# Iout.net
KiCad netlist of a schematic drawn in Altium Designer
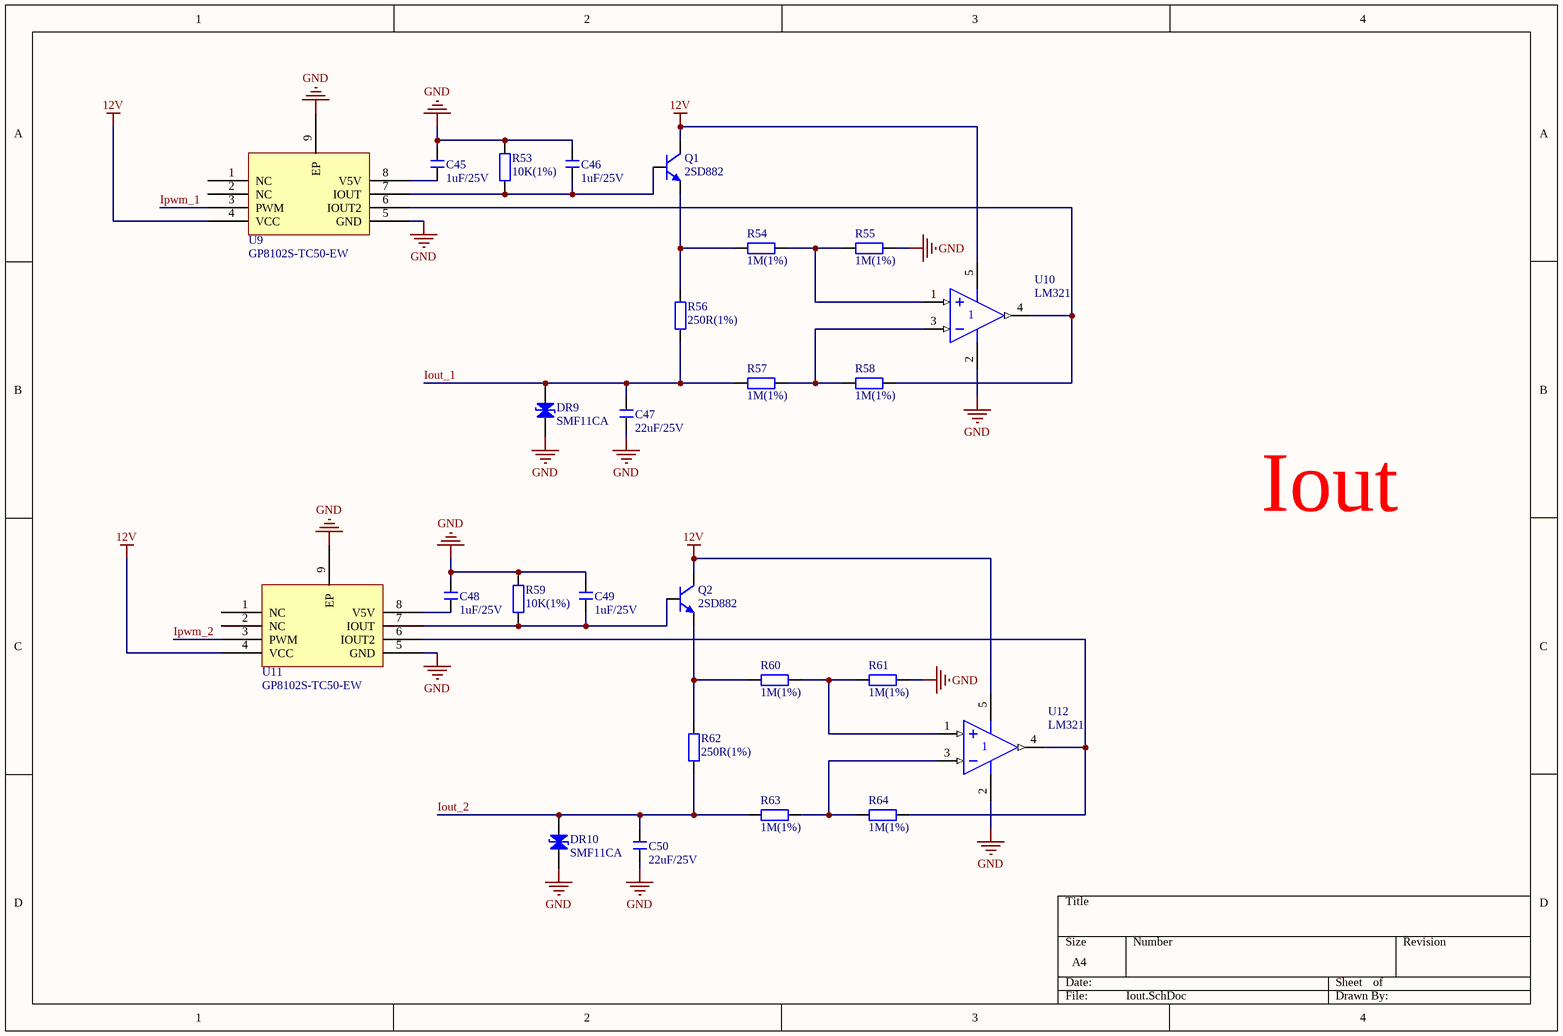
[diagram p0: Iout.SchDoc]

(export (version "E")
  (design (tool "Eeschema 10.0.6"))
  (components
    (comp (ref "C45")
      (value "1uF/25V")
      (footprint "C 0603_L")
      (description "无极性贴片电容")
      (fields (field (name "版权归属") "源创客"))
      (libsource (lib "电阻-电容-电感") (part "C"))
    )
    (comp (ref "C46")
      (value "1uF/25V")
      (footprint "C 0603_L")
      (description "无极性贴片电容")
      (fields (field (name "版权归属") "源创客"))
      (libsource (lib "电阻-电容-电感") (part "C"))
    )
    (comp (ref "C47")
      (value "22uF/25V")
      (footprint "C 0603_L")
      (description "无极性贴片电容")
      (fields (field (name "版权归属") "源创客"))
      (libsource (lib "电阻-电容-电感") (part "C"))
    )
    (comp (ref "C48")
      (value "1uF/25V")
      (footprint "C 0603_L")
      (description "无极性贴片电容")
      (fields (field (name "版权归属") "源创客"))
      (libsource (lib "电阻-电容-电感") (part "C"))
    )
    (comp (ref "C49")
      (value "1uF/25V")
      (footprint "C 0603_L")
      (description "无极性贴片电容")
      (fields (field (name "版权归属") "源创客"))
      (libsource (lib "电阻-电容-电感") (part "C"))
    )
    (comp (ref "C50")
      (value "22uF/25V")
      (footprint "C 0603_L")
      (description "无极性贴片电容")
      (fields (field (name "版权归属") "源创客"))
      (libsource (lib "电阻-电容-电感") (part "C"))
    )
    (comp (ref "DR9")
      (value "SMF11CA")
      (footprint "SOD-123F")
      (description "瞬态电压抑制二极管")
      (fields (field (name "版权归属") "源创客"))
      (libsource (lib "二极管-整流桥") (part "DR"))
    )
    (comp (ref "DR10")
      (value "SMF11CA")
      (footprint "SOD-123F")
      (description "瞬态电压抑制二极管")
      (fields (field (name "版权归属") "源创客"))
      (libsource (lib "二极管-整流桥") (part "DR"))
    )
    (comp (ref "Q1")
      (value "2SD882")
      (footprint "SOT89_N")
      (description "音频功放-NPN型")
      (fields (field (name "版权归属") "源创客"))
      (libsource (lib "三极管") (part "D882-SMD"))
    )
    (comp (ref "Q2")
      (value "2SD882")
      (footprint "SOT89_N")
      (description "音频功放-NPN型")
      (fields (field (name "版权归属") "源创客"))
      (libsource (lib "三极管") (part "D882-SMD"))
    )
    (comp (ref "R53")
      (value "10K(1%)")
      (footprint "R 0603_L")
      (description "贴片电阻")
      (fields (field (name "版权归属") "源创客"))
      (libsource (lib "电阻-电容-电感") (part "R"))
    )
    (comp (ref "R54")
      (value "1M(1%)")
      (footprint "R 0603_L")
      (description "贴片电阻")
      (fields (field (name "版权归属") "源创客"))
      (libsource (lib "电阻-电容-电感") (part "R"))
    )
    (comp (ref "R55")
      (value "1M(1%)")
      (footprint "R 0603_L")
      (description "贴片电阻")
      (fields (field (name "版权归属") "源创客"))
      (libsource (lib "电阻-电容-电感") (part "R"))
    )
    (comp (ref "R56")
      (value "250R(1%)")
      (footprint "R 0603_L")
      (description "贴片电阻")
      (fields (field (name "版权归属") "源创客"))
      (libsource (lib "电阻-电容-电感") (part "R"))
    )
    (comp (ref "R57")
      (value "1M(1%)")
      (footprint "R 0603_L")
      (description "贴片电阻")
      (fields (field (name "版权归属") "源创客"))
      (libsource (lib "电阻-电容-电感") (part "R"))
    )
    (comp (ref "R58")
      (value "1M(1%)")
      (footprint "R 0603_L")
      (description "贴片电阻")
      (fields (field (name "版权归属") "源创客"))
      (libsource (lib "电阻-电容-电感") (part "R"))
    )
    (comp (ref "R59")
      (value "10K(1%)")
      (footprint "R 0603_L")
      (description "贴片电阻")
      (fields (field (name "版权归属") "源创客"))
      (libsource (lib "电阻-电容-电感") (part "R"))
    )
    (comp (ref "R60")
      (value "1M(1%)")
      (footprint "R 0603_L")
      (description "贴片电阻")
      (fields (field (name "版权归属") "源创客"))
      (libsource (lib "电阻-电容-电感") (part "R"))
    )
    (comp (ref "R61")
      (value "1M(1%)")
      (footprint "R 0603_L")
      (description "贴片电阻")
      (fields (field (name "版权归属") "源创客"))
      (libsource (lib "电阻-电容-电感") (part "R"))
    )
    (comp (ref "R62")
      (value "250R(1%)")
      (footprint "R 0603_L")
      (description "贴片电阻")
      (fields (field (name "版权归属") "源创客"))
      (libsource (lib "电阻-电容-电感") (part "R"))
    )
    (comp (ref "R63")
      (value "1M(1%)")
      (footprint "R 0603_L")
      (description "贴片电阻")
      (fields (field (name "版权归属") "源创客"))
      (libsource (lib "电阻-电容-电感") (part "R"))
    )
    (comp (ref "R64")
      (value "1M(1%)")
      (footprint "R 0603_L")
      (description "贴片电阻")
      (fields (field (name "版权归属") "源创客"))
      (libsource (lib "电阻-电容-电感") (part "R"))
    )
    (comp (ref "U9")
      (value "GP8102S-TC50-EW")
      (footprint "ESOP8_N")
      (libsource (lib "MICB") (part "GP8102S-TC50-EW"))
    )
    (comp (ref "U10") (value "LM321") (footprint "SOT23-5N") (libsource (lib "MICB") (part "LM321")))
    (comp (ref "U11")
      (value "GP8102S-TC50-EW")
      (footprint "ESOP8_N")
      (libsource (lib "MICB") (part "GP8102S-TC50-EW"))
    )
    (comp (ref "U12") (value "LM321") (footprint "SOT23-5N") (libsource (lib "MICB") (part "LM321")))
  )
  (nets
    (net (code "1") (name "/Iout_1") (class "Default")
      (node (ref "C47") (pin "1") (pinfunction "1_1") (pintype "passive"))
      (node (ref "DR9") (pin "1") (pinfunction "A_1") (pintype "passive"))
      (node (ref "R56") (pin "2") (pinfunction "2_2") (pintype "passive"))
      (node (ref "R57") (pin "1") (pinfunction "1_1") (pintype "passive"))
    )
    (net (code "2") (name "/Iout_2") (class "Default")
      (node (ref "C50") (pin "1") (pinfunction "1_1") (pintype "passive"))
      (node (ref "DR10") (pin "1") (pinfunction "A_1") (pintype "passive"))
      (node (ref "R62") (pin "2") (pinfunction "2_2") (pintype "passive"))
      (node (ref "R63") (pin "1") (pinfunction "1_1") (pintype "passive"))
    )
    (net (code "3") (name "/Ipwm_1") (class "Default")
      (node (ref "U9") (pin "3") (pinfunction "PWM_3") (pintype "passive"))
    )
    (net (code "4") (name "/Ipwm_2") (class "Default")
      (node (ref "U11") (pin "3") (pinfunction "PWM_3") (pintype "passive"))
    )
    (net (code "5") (name "12V") (class "Default")
      (node (ref "Q1") (pin "2") (pinfunction "C_2") (pintype "passive"))
      (node (ref "Q2") (pin "2") (pinfunction "C_2") (pintype "passive"))
      (node (ref "U10") (pin "5") (pinfunction "V+_5") (pintype "power_in"))
      (node (ref "U11") (pin "4") (pinfunction "VCC_4") (pintype "passive"))
      (node (ref "U12") (pin "5") (pinfunction "V+_5") (pintype "power_in"))
      (node (ref "U9") (pin "4") (pinfunction "VCC_4") (pintype "passive"))
    )
    (net (code "6") (name "GND") (class "Default")
      (node (ref "C45") (pin "2") (pinfunction "2_2") (pintype "passive"))
      (node (ref "C46") (pin "2") (pinfunction "2_2") (pintype "passive"))
      (node (ref "C47") (pin "2") (pinfunction "2_2") (pintype "passive"))
      (node (ref "C48") (pin "2") (pinfunction "2_2") (pintype "passive"))
      (node (ref "C49") (pin "2") (pinfunction "2_2") (pintype "passive"))
      (node (ref "C50") (pin "2") (pinfunction "2_2") (pintype "passive"))
      (node (ref "DR10") (pin "2") (pinfunction "K_2") (pintype "passive"))
      (node (ref "DR9") (pin "2") (pinfunction "K_2") (pintype "passive"))
      (node (ref "R53") (pin "2") (pinfunction "2_2") (pintype "passive"))
      (node (ref "R55") (pin "2") (pinfunction "2_2") (pintype "passive"))
      (node (ref "R59") (pin "2") (pinfunction "2_2") (pintype "passive"))
      (node (ref "R61") (pin "2") (pinfunction "2_2") (pintype "passive"))
      (node (ref "U10") (pin "2") (pinfunction "V-_2") (pintype "power_in"))
      (node (ref "U11") (pin "5") (pinfunction "GND_5") (pintype "passive"))
      (node (ref "U11") (pin "9") (pinfunction "EP_9") (pintype "passive"))
      (node (ref "U12") (pin "2") (pinfunction "V-_2") (pintype "power_in"))
      (node (ref "U9") (pin "5") (pinfunction "GND_5") (pintype "passive"))
      (node (ref "U9") (pin "9") (pinfunction "EP_9") (pintype "passive"))
    )
    (net (code "7") (name "Net-(Q1-B)") (class "Default")
      (node (ref "C46") (pin "1") (pinfunction "1_1") (pintype "passive"))
      (node (ref "Q1") (pin "1") (pinfunction "B_1") (pintype "passive"))
      (node (ref "R53") (pin "1") (pinfunction "1_1") (pintype "passive"))
      (node (ref "U9") (pin "7") (pinfunction "IOUT_7") (pintype "passive"))
    )
    (net (code "8") (name "Net-(Q1-E)") (class "Default")
      (node (ref "Q1") (pin "3") (pinfunction "E_3") (pintype "passive"))
      (node (ref "R54") (pin "1") (pinfunction "1_1") (pintype "passive"))
      (node (ref "R56") (pin "1") (pinfunction "1_1") (pintype "passive"))
    )
    (net (code "9") (name "Net-(Q2-B)") (class "Default")
      (node (ref "C49") (pin "1") (pinfunction "1_1") (pintype "passive"))
      (node (ref "Q2") (pin "1") (pinfunction "B_1") (pintype "passive"))
      (node (ref "R59") (pin "1") (pinfunction "1_1") (pintype "passive"))
      (node (ref "U11") (pin "7") (pinfunction "IOUT_7") (pintype "passive"))
    )
    (net (code "10") (name "Net-(Q2-E)") (class "Default")
      (node (ref "Q2") (pin "3") (pinfunction "E_3") (pintype "passive"))
      (node (ref "R60") (pin "1") (pinfunction "1_1") (pintype "passive"))
      (node (ref "R62") (pin "1") (pinfunction "1_1") (pintype "passive"))
    )
    (net (code "11") (name "Net-(U9-V5V)") (class "Default")
      (node (ref "C45") (pin "1") (pinfunction "1_1") (pintype "passive"))
      (node (ref "U9") (pin "8") (pinfunction "V5V_8") (pintype "passive"))
    )
    (net (code "12") (name "Net-(U10-IN+)") (class "Default")
      (node (ref "R54") (pin "2") (pinfunction "2_2") (pintype "passive"))
      (node (ref "R55") (pin "1") (pinfunction "1_1") (pintype "passive"))
      (node (ref "U10") (pin "1") (pinfunction "IN+_1") (pintype "input"))
    )
    (net (code "13") (name "Net-(U10-IN-)") (class "Default")
      (node (ref "R57") (pin "2") (pinfunction "2_2") (pintype "passive"))
      (node (ref "R58") (pin "1") (pinfunction "1_1") (pintype "passive"))
      (node (ref "U10") (pin "3") (pinfunction "IN-_3") (pintype "input"))
    )
    (net (code "14") (name "Net-(U10-OUT)") (class "Default")
      (node (ref "R58") (pin "2") (pinfunction "2_2") (pintype "passive"))
      (node (ref "U10") (pin "4") (pinfunction "OUT_4") (pintype "output"))
      (node (ref "U9") (pin "6") (pinfunction "IOUT2_6") (pintype "passive"))
    )
    (net (code "15") (name "Net-(U11-IOUT2)") (class "Default")
      (node (ref "R64") (pin "2") (pinfunction "2_2") (pintype "passive"))
      (node (ref "U11") (pin "6") (pinfunction "IOUT2_6") (pintype "passive"))
      (node (ref "U12") (pin "4") (pinfunction "OUT_4") (pintype "output"))
    )
    (net (code "16") (name "Net-(U11-V5V)") (class "Default")
      (node (ref "C48") (pin "1") (pinfunction "1_1") (pintype "passive"))
      (node (ref "U11") (pin "8") (pinfunction "V5V_8") (pintype "passive"))
    )
    (net (code "17") (name "Net-(U12-IN+)") (class "Default")
      (node (ref "R60") (pin "2") (pinfunction "2_2") (pintype "passive"))
      (node (ref "R61") (pin "1") (pinfunction "1_1") (pintype "passive"))
      (node (ref "U12") (pin "1") (pinfunction "IN+_1") (pintype "input"))
    )
    (net (code "18") (name "Net-(U12-IN-)") (class "Default")
      (node (ref "R63") (pin "2") (pinfunction "2_2") (pintype "passive"))
      (node (ref "R64") (pin "1") (pinfunction "1_1") (pintype "passive"))
      (node (ref "U12") (pin "3") (pinfunction "IN-_3") (pintype "input"))
    )
    (net (code "19") (name "unconnected-(U9-NC-Pad1)") (class "Default")
      (node (ref "U9") (pin "1") (pinfunction "NC_1") (pintype "passive"))
    )
    (net (code "20") (name "unconnected-(U9-NC-Pad2)") (class "Default")
      (node (ref "U9") (pin "2") (pinfunction "NC_2") (pintype "passive"))
    )
    (net (code "21") (name "unconnected-(U11-NC-Pad1)") (class "Default")
      (node (ref "U11") (pin "1") (pinfunction "NC_1") (pintype "passive"))
    )
    (net (code "22") (name "unconnected-(U11-NC-Pad2)") (class "Default")
      (node (ref "U11") (pin "2") (pinfunction "NC_2") (pintype "passive"))
    )
  )
)
